# school_shield.net
KiCad netlist of a schematic drawn in EAGLE
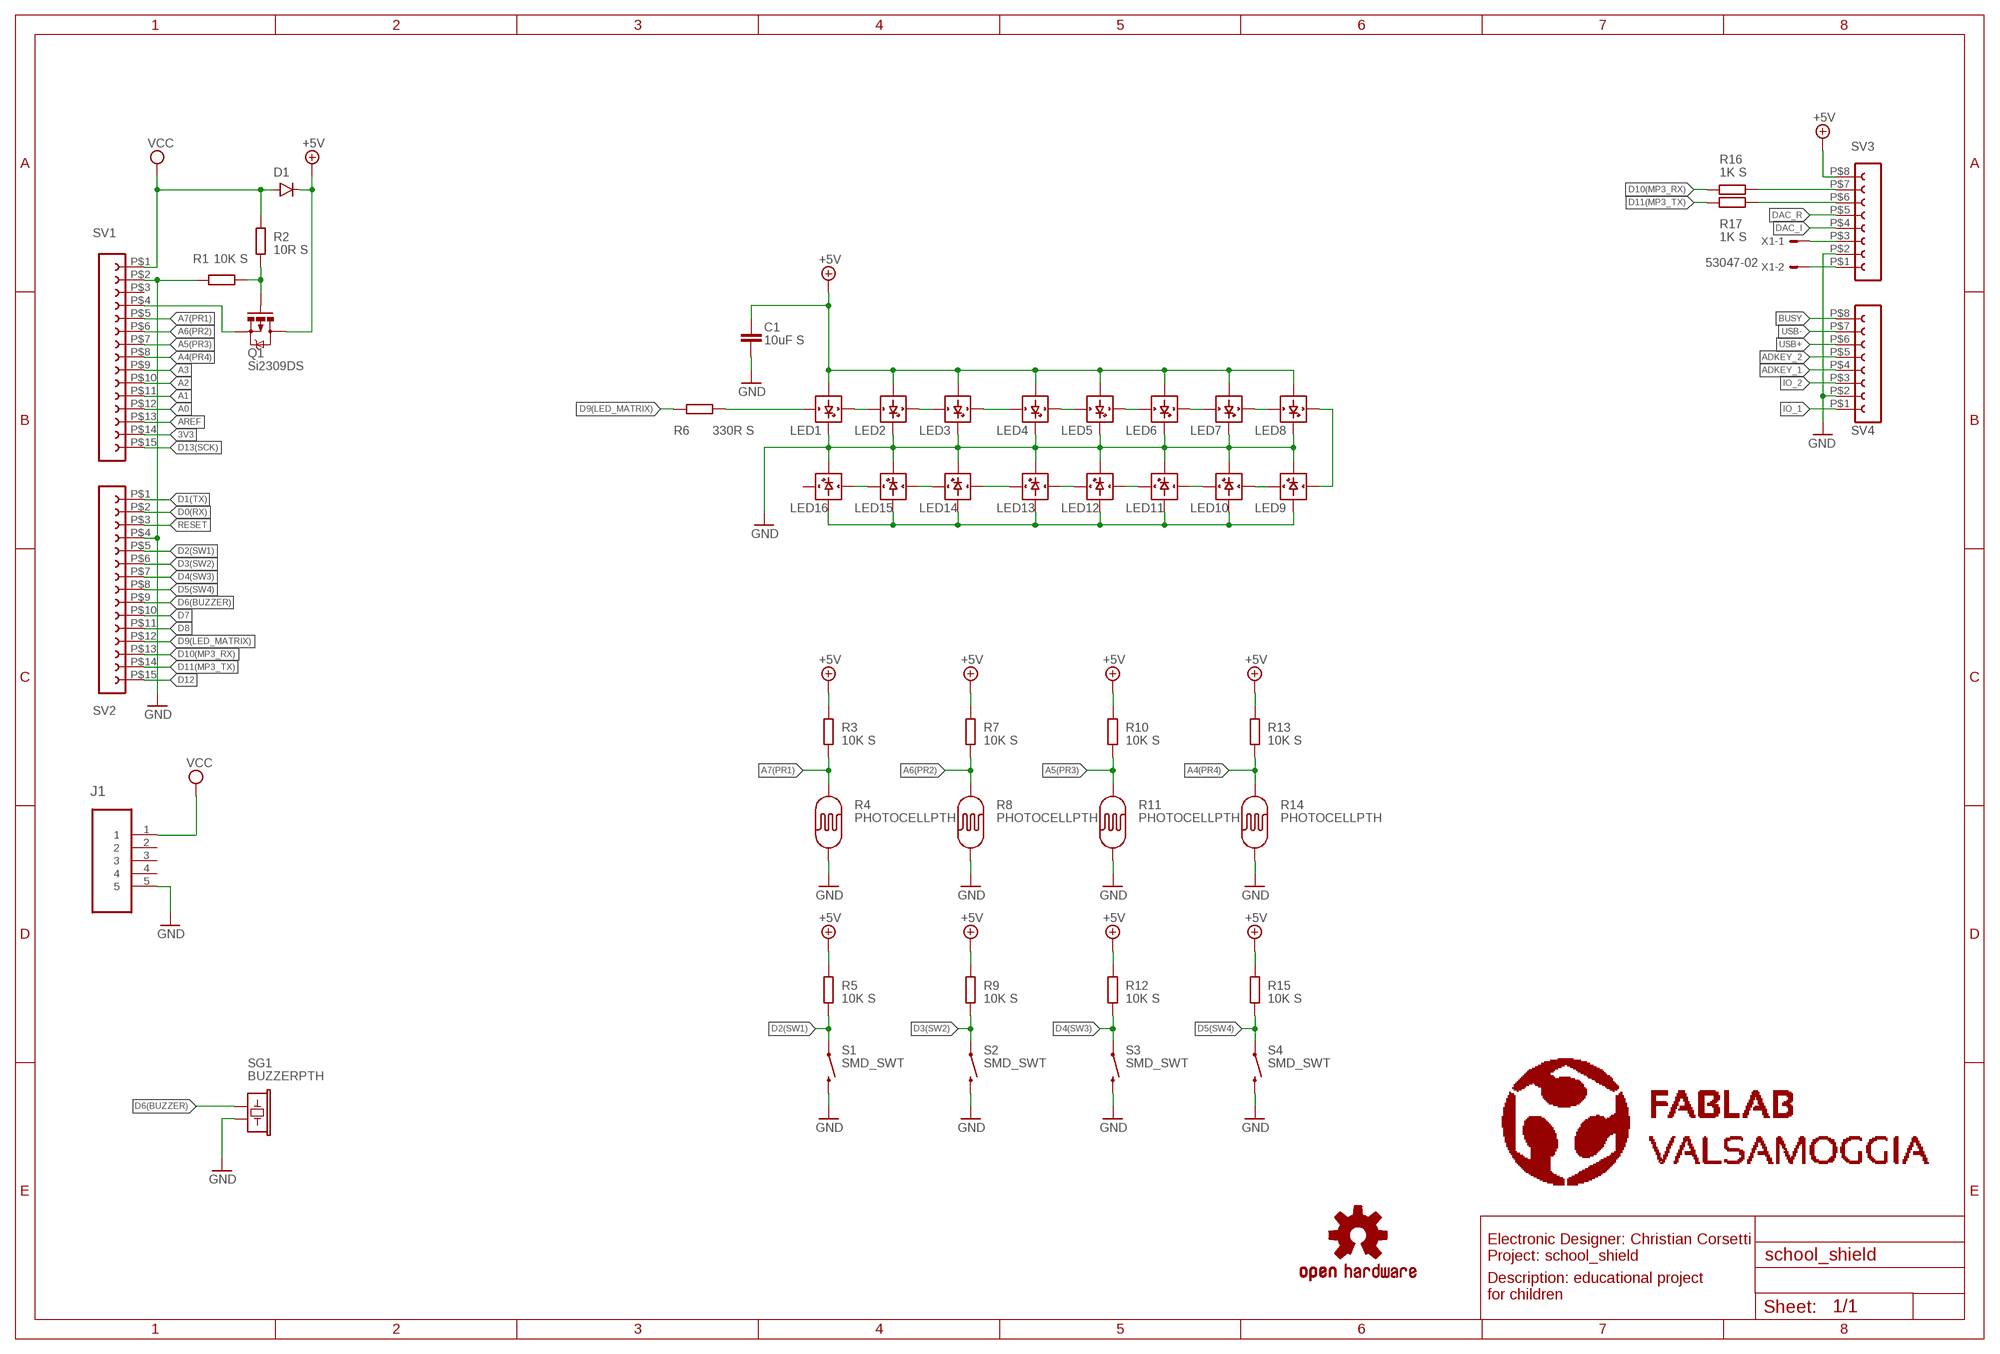
[diagram p0: schematic, sheet 1]

(export (version "E")
  (design (tool "Eeschema 10.0.6"))
  (components
    (comp (ref "C1")
      (value "10uF S")
      (footprint "eagle-import:C0805")
      (libsource (lib "eagle-import") (part "C-EUC0805"))
    )
    (comp (ref "D1")
      (value "DIODESMA")
      (footprint "eagle-import:SMA-DIODE")
      (libsource (lib "eagle-import") (part "DIODESMA"))
    )
    (comp (ref "J1")
      (value "47346-0001")
      (footprint "eagle-import:MOLEX_47346-0001")
      (fields (field (name "SPICEPREFIX") "X"))
      (libsource (lib "eagle-import") (part "47346-0001"))
    )
    (comp (ref "LED1")
      (value "WS2812B_ALT")
      (footprint "eagle-import:WS2812B")
      (libsource (lib "eagle-import") (part "WS2812B_ALT"))
    )
    (comp (ref "LED2")
      (value "WS2812B_ALT")
      (footprint "eagle-import:WS2812B")
      (libsource (lib "eagle-import") (part "WS2812B_ALT"))
    )
    (comp (ref "LED3")
      (value "WS2812B_ALT")
      (footprint "eagle-import:WS2812B")
      (libsource (lib "eagle-import") (part "WS2812B_ALT"))
    )
    (comp (ref "LED4")
      (value "WS2812B_ALT")
      (footprint "eagle-import:WS2812B")
      (libsource (lib "eagle-import") (part "WS2812B_ALT"))
    )
    (comp (ref "LED5")
      (value "WS2812B_ALT")
      (footprint "eagle-import:WS2812B")
      (libsource (lib "eagle-import") (part "WS2812B_ALT"))
    )
    (comp (ref "LED6")
      (value "WS2812B_ALT")
      (footprint "eagle-import:WS2812B")
      (libsource (lib "eagle-import") (part "WS2812B_ALT"))
    )
    (comp (ref "LED7")
      (value "WS2812B_ALT")
      (footprint "eagle-import:WS2812B")
      (libsource (lib "eagle-import") (part "WS2812B_ALT"))
    )
    (comp (ref "LED8")
      (value "WS2812B_ALT")
      (footprint "eagle-import:WS2812B")
      (libsource (lib "eagle-import") (part "WS2812B_ALT"))
    )
    (comp (ref "LED9")
      (value "WS2812B_ALT")
      (footprint "eagle-import:WS2812B")
      (libsource (lib "eagle-import") (part "WS2812B_ALT"))
    )
    (comp (ref "LED10")
      (value "WS2812B_ALT")
      (footprint "eagle-import:WS2812B")
      (libsource (lib "eagle-import") (part "WS2812B_ALT"))
    )
    (comp (ref "LED11")
      (value "WS2812B_ALT")
      (footprint "eagle-import:WS2812B")
      (libsource (lib "eagle-import") (part "WS2812B_ALT"))
    )
    (comp (ref "LED12")
      (value "WS2812B_ALT")
      (footprint "eagle-import:WS2812B")
      (libsource (lib "eagle-import") (part "WS2812B_ALT"))
    )
    (comp (ref "LED13")
      (value "WS2812B_ALT")
      (footprint "eagle-import:WS2812B")
      (libsource (lib "eagle-import") (part "WS2812B_ALT"))
    )
    (comp (ref "LED14")
      (value "WS2812B_ALT")
      (footprint "eagle-import:WS2812B")
      (libsource (lib "eagle-import") (part "WS2812B_ALT"))
    )
    (comp (ref "LED15")
      (value "WS2812B_ALT")
      (footprint "eagle-import:WS2812B")
      (libsource (lib "eagle-import") (part "WS2812B_ALT"))
    )
    (comp (ref "LED16")
      (value "WS2812B_ALT")
      (footprint "eagle-import:WS2812B")
      (libsource (lib "eagle-import") (part "WS2812B_ALT"))
    )
    (comp (ref "LOGO1")
      (value "OSHW-LOGOMINI")
      (footprint "eagle-import:OSHW-LOGO-MINI")
      (libsource (lib "eagle-import") (part "OSHW-LOGOMINI"))
    )
    (comp (ref "Q1")
      (value "Si2309DS")
      (footprint "eagle-import:SOT23-3")
      (libsource (lib "eagle-import") (part "MOSFET-PCHANNELSMD"))
    )
    (comp (ref "R1")
      (value "10K S")
      (footprint "eagle-import:R0805")
      (libsource (lib "eagle-import") (part "R-EU_R0805"))
    )
    (comp (ref "R2")
      (value "10R S")
      (footprint "eagle-import:R0805")
      (libsource (lib "eagle-import") (part "R-EU_R0805"))
    )
    (comp (ref "R3")
      (value "10K S")
      (footprint "eagle-import:R0805")
      (libsource (lib "eagle-import") (part "R-EU_R0805"))
    )
    (comp (ref "R4")
      (value "PHOTOCELLPTH")
      (footprint "eagle-import:PHOTOCELL")
      (libsource (lib "eagle-import") (part "PHOTOCELLPTH"))
    )
    (comp (ref "R5")
      (value "10K S")
      (footprint "eagle-import:R0805")
      (libsource (lib "eagle-import") (part "R-EU_R0805"))
    )
    (comp (ref "R6")
      (value "330R S")
      (footprint "eagle-import:R0805")
      (libsource (lib "eagle-import") (part "R-EU_R0805"))
    )
    (comp (ref "R7")
      (value "10K S")
      (footprint "eagle-import:R0805")
      (libsource (lib "eagle-import") (part "R-EU_R0805"))
    )
    (comp (ref "R8")
      (value "PHOTOCELLPTH")
      (footprint "eagle-import:PHOTOCELL")
      (libsource (lib "eagle-import") (part "PHOTOCELLPTH"))
    )
    (comp (ref "R9")
      (value "10K S")
      (footprint "eagle-import:R0805")
      (libsource (lib "eagle-import") (part "R-EU_R0805"))
    )
    (comp (ref "R10")
      (value "10K S")
      (footprint "eagle-import:R0805")
      (libsource (lib "eagle-import") (part "R-EU_R0805"))
    )
    (comp (ref "R11")
      (value "PHOTOCELLPTH")
      (footprint "eagle-import:PHOTOCELL")
      (libsource (lib "eagle-import") (part "PHOTOCELLPTH"))
    )
    (comp (ref "R12")
      (value "10K S")
      (footprint "eagle-import:R0805")
      (libsource (lib "eagle-import") (part "R-EU_R0805"))
    )
    (comp (ref "R13")
      (value "10K S")
      (footprint "eagle-import:R0805")
      (libsource (lib "eagle-import") (part "R-EU_R0805"))
    )
    (comp (ref "R14")
      (value "PHOTOCELLPTH")
      (footprint "eagle-import:PHOTOCELL")
      (libsource (lib "eagle-import") (part "PHOTOCELLPTH"))
    )
    (comp (ref "R15")
      (value "10K S")
      (footprint "eagle-import:R0805")
      (libsource (lib "eagle-import") (part "R-EU_R0805"))
    )
    (comp (ref "R16")
      (value "1K S")
      (footprint "eagle-import:R0805")
      (libsource (lib "eagle-import") (part "R-EU_R0805"))
    )
    (comp (ref "R17")
      (value "1K S")
      (footprint "eagle-import:R0805")
      (libsource (lib "eagle-import") (part "R-EU_R0805"))
    )
    (comp (ref "S1")
      (value "SMD_SWT")
      (footprint "eagle-import:TACTILE_SWITCH_TALL")
      (libsource (lib "eagle-import") (part "SWITCH-MOMENTARY-2SMD-4"))
    )
    (comp (ref "S2")
      (value "SMD_SWT")
      (footprint "eagle-import:TACTILE_SWITCH_TALL")
      (libsource (lib "eagle-import") (part "SWITCH-MOMENTARY-2SMD-4"))
    )
    (comp (ref "S3")
      (value "SMD_SWT")
      (footprint "eagle-import:TACTILE_SWITCH_TALL")
      (libsource (lib "eagle-import") (part "SWITCH-MOMENTARY-2SMD-4"))
    )
    (comp (ref "S4")
      (value "SMD_SWT")
      (footprint "eagle-import:TACTILE_SWITCH_TALL")
      (libsource (lib "eagle-import") (part "SWITCH-MOMENTARY-2SMD-4"))
    )
    (comp (ref "SG1")
      (value "BUZZERPTH")
      (footprint "eagle-import:BUZZER-12MM")
      (libsource (lib "eagle-import") (part "BUZZERPTH"))
    )
    (comp (ref "SV1")
      (value "FE15-1SMD")
      (footprint "eagle-import:FE15_SMD")
      (libsource (lib "eagle-import") (part "FE15-1SMD"))
    )
    (comp (ref "SV2")
      (value "FE15-1SMD")
      (footprint "eagle-import:FE15_SMD")
      (libsource (lib "eagle-import") (part "FE15-1SMD"))
    )
    (comp (ref "SV3")
      (value "FE08-1SMD")
      (footprint "eagle-import:FE08_SMD")
      (libsource (lib "eagle-import") (part "FE08-1SMD"))
    )
    (comp (ref "SV4")
      (value "FE08-1SMD")
      (footprint "eagle-import:FE08_SMD")
      (libsource (lib "eagle-import") (part "FE08-1SMD"))
    )
    (comp (ref "U$1")
      (value "FABLAB")
      (footprint "eagle-import:FABLAB")
      (libsource (lib "eagle-import") (part "FABLAB"))
    )
    (comp (ref "X1")
      (value "53047-02")
      (footprint "eagle-import:53047-02")
      (libsource (lib "eagle-import") (part "53?-02047"))
    )
  )
  (nets
    (net (code "1") (name "+5V") (class "Default")
      (node (ref "C1") (pin "2") (pinfunction "2_2") (pintype "passive"))
      (node (ref "D1") (pin "C") (pinfunction "C_C") (pintype "passive"))
      (node (ref "LED1") (pin "1-VDD") (pinfunction "VDD_1-VDD") (pintype "bidirectional"))
      (node (ref "LED2") (pin "1-VDD") (pinfunction "VDD_1-VDD") (pintype "bidirectional"))
      (node (ref "LED3") (pin "1-VDD") (pinfunction "VDD_1-VDD") (pintype "bidirectional"))
      (node (ref "LED4") (pin "1-VDD") (pinfunction "VDD_1-VDD") (pintype "bidirectional"))
      (node (ref "LED5") (pin "1-VDD") (pinfunction "VDD_1-VDD") (pintype "bidirectional"))
      (node (ref "LED6") (pin "1-VDD") (pinfunction "VDD_1-VDD") (pintype "bidirectional"))
      (node (ref "LED7") (pin "1-VDD") (pinfunction "VDD_1-VDD") (pintype "bidirectional"))
      (node (ref "LED8") (pin "1-VDD") (pinfunction "VDD_1-VDD") (pintype "bidirectional"))
      (node (ref "Q1") (pin "3") (pinfunction "D_3") (pintype "passive"))
      (node (ref "R10") (pin "2") (pinfunction "2_2") (pintype "passive"))
      (node (ref "R12") (pin "2") (pinfunction "2_2") (pintype "passive"))
      (node (ref "R13") (pin "2") (pinfunction "2_2") (pintype "passive"))
      (node (ref "R15") (pin "2") (pinfunction "2_2") (pintype "passive"))
      (node (ref "R3") (pin "2") (pinfunction "2_2") (pintype "passive"))
      (node (ref "R5") (pin "2") (pinfunction "2_2") (pintype "passive"))
      (node (ref "R7") (pin "2") (pinfunction "2_2") (pintype "passive"))
      (node (ref "R9") (pin "2") (pinfunction "2_2") (pintype "passive"))
      (node (ref "SV3") (pin "P$8") (pinfunction "8_P$8") (pintype "passive"))
    )
    (net (code "2") (name "3V3") (class "Default")
      (node (ref "SV1") (pin "P$14") (pinfunction "14_P$14") (pintype "passive"))
    )
    (net (code "3") (name "A0") (class "Default")
      (node (ref "SV1") (pin "P$12") (pinfunction "12_P$12") (pintype "passive"))
    )
    (net (code "4") (name "A1") (class "Default")
      (node (ref "SV1") (pin "P$11") (pinfunction "11_P$11") (pintype "passive"))
    )
    (net (code "5") (name "A2") (class "Default")
      (node (ref "SV1") (pin "P$10") (pinfunction "10_P$10") (pintype "passive"))
    )
    (net (code "6") (name "A3") (class "Default")
      (node (ref "SV1") (pin "P$9") (pinfunction "9_P$9") (pintype "passive"))
    )
    (net (code "7") (name "A4(PR4)") (class "Default")
      (node (ref "R13") (pin "1") (pinfunction "1_1") (pintype "passive"))
      (node (ref "R14") (pin "2") (pinfunction "P$2_2") (pintype "bidirectional"))
      (node (ref "SV1") (pin "P$8") (pinfunction "8_P$8") (pintype "passive"))
    )
    (net (code "8") (name "A5(PR3)") (class "Default")
      (node (ref "R10") (pin "1") (pinfunction "1_1") (pintype "passive"))
      (node (ref "R11") (pin "2") (pinfunction "P$2_2") (pintype "bidirectional"))
      (node (ref "SV1") (pin "P$7") (pinfunction "7_P$7") (pintype "passive"))
    )
    (net (code "9") (name "A6(PR2)") (class "Default")
      (node (ref "R7") (pin "1") (pinfunction "1_1") (pintype "passive"))
      (node (ref "R8") (pin "2") (pinfunction "P$2_2") (pintype "bidirectional"))
      (node (ref "SV1") (pin "P$6") (pinfunction "6_P$6") (pintype "passive"))
    )
    (net (code "10") (name "A7(PR1)") (class "Default")
      (node (ref "R3") (pin "1") (pinfunction "1_1") (pintype "passive"))
      (node (ref "R4") (pin "2") (pinfunction "P$2_2") (pintype "bidirectional"))
      (node (ref "SV1") (pin "P$5") (pinfunction "5_P$5") (pintype "passive"))
    )
    (net (code "11") (name "ADKEY_1") (class "Default")
      (node (ref "SV4") (pin "P$4") (pinfunction "4_P$4") (pintype "passive"))
    )
    (net (code "12") (name "ADKEY_2") (class "Default")
      (node (ref "SV4") (pin "P$5") (pinfunction "5_P$5") (pintype "passive"))
    )
    (net (code "13") (name "AREF") (class "Default")
      (node (ref "SV1") (pin "P$13") (pinfunction "13_P$13") (pintype "passive"))
    )
    (net (code "14") (name "BUSY") (class "Default")
      (node (ref "SV4") (pin "P$8") (pinfunction "8_P$8") (pintype "passive"))
    )
    (net (code "15") (name "D0(RX)") (class "Default")
      (node (ref "SV2") (pin "P$2") (pinfunction "2_P$2") (pintype "passive"))
    )
    (net (code "16") (name "D1(TX)") (class "Default")
      (node (ref "SV2") (pin "P$1") (pinfunction "1_P$1") (pintype "passive"))
    )
    (net (code "17") (name "D2(SW1)") (class "Default")
      (node (ref "R5") (pin "1") (pinfunction "1_1") (pintype "passive"))
      (node (ref "S1") (pin "A2") (pinfunction "1_A2") (pintype "passive"))
      (node (ref "SV2") (pin "P$5") (pinfunction "5_P$5") (pintype "passive"))
    )
    (net (code "18") (name "D3(SW2)") (class "Default")
      (node (ref "R9") (pin "1") (pinfunction "1_1") (pintype "passive"))
      (node (ref "S2") (pin "A2") (pinfunction "1_A2") (pintype "passive"))
      (node (ref "SV2") (pin "P$6") (pinfunction "6_P$6") (pintype "passive"))
    )
    (net (code "19") (name "D4(SW3)") (class "Default")
      (node (ref "R12") (pin "1") (pinfunction "1_1") (pintype "passive"))
      (node (ref "S3") (pin "A2") (pinfunction "1_A2") (pintype "passive"))
      (node (ref "SV2") (pin "P$7") (pinfunction "7_P$7") (pintype "passive"))
    )
    (net (code "20") (name "D5(SW4)") (class "Default")
      (node (ref "R15") (pin "1") (pinfunction "1_1") (pintype "passive"))
      (node (ref "S4") (pin "A2") (pinfunction "1_A2") (pintype "passive"))
      (node (ref "SV2") (pin "P$8") (pinfunction "8_P$8") (pintype "passive"))
    )
    (net (code "21") (name "D6(BUZZER)") (class "Default")
      (node (ref "SG1") (pin "+") (pinfunction "1_+") (pintype "passive"))
      (node (ref "SV2") (pin "P$9") (pinfunction "9_P$9") (pintype "passive"))
    )
    (net (code "22") (name "D7") (class "Default")
      (node (ref "SV2") (pin "P$10") (pinfunction "10_P$10") (pintype "passive"))
    )
    (net (code "23") (name "D8") (class "Default")
      (node (ref "SV2") (pin "P$11") (pinfunction "11_P$11") (pintype "passive"))
    )
    (net (code "24") (name "D9(LED_MATRIX)") (class "Default")
      (node (ref "R6") (pin "2") (pinfunction "2_2") (pintype "passive"))
      (node (ref "SV2") (pin "P$12") (pinfunction "12_P$12") (pintype "passive"))
    )
    (net (code "25") (name "D10(MP3_RX)") (class "Default")
      (node (ref "R16") (pin "2") (pinfunction "2_2") (pintype "passive"))
      (node (ref "SV2") (pin "P$13") (pinfunction "13_P$13") (pintype "passive"))
    )
    (net (code "26") (name "D11(MP3_TX)") (class "Default")
      (node (ref "R17") (pin "2") (pinfunction "2_2") (pintype "passive"))
      (node (ref "SV2") (pin "P$14") (pinfunction "14_P$14") (pintype "passive"))
    )
    (net (code "27") (name "D12") (class "Default")
      (node (ref "SV2") (pin "P$15") (pinfunction "15_P$15") (pintype "passive"))
    )
    (net (code "28") (name "D13(SCK)") (class "Default")
      (node (ref "SV1") (pin "P$15") (pinfunction "15_P$15") (pintype "passive"))
    )
    (net (code "29") (name "DAC_I") (class "Default")
      (node (ref "SV3") (pin "P$4") (pinfunction "4_P$4") (pintype "passive"))
    )
    (net (code "30") (name "DAC_R") (class "Default")
      (node (ref "SV3") (pin "P$5") (pinfunction "5_P$5") (pintype "passive"))
    )
    (net (code "31") (name "GND") (class "Default")
      (node (ref "C1") (pin "1") (pinfunction "1_1") (pintype "passive"))
      (node (ref "J1") (pin "5") (pinfunction "5_5") (pintype "input"))
      (node (ref "LED1") (pin "3-GND") (pinfunction "GND_3-GND") (pintype "bidirectional"))
      (node (ref "LED10") (pin "3-GND") (pinfunction "GND_3-GND") (pintype "bidirectional"))
      (node (ref "LED11") (pin "3-GND") (pinfunction "GND_3-GND") (pintype "bidirectional"))
      (node (ref "LED12") (pin "3-GND") (pinfunction "GND_3-GND") (pintype "bidirectional"))
      (node (ref "LED13") (pin "3-GND") (pinfunction "GND_3-GND") (pintype "bidirectional"))
      (node (ref "LED14") (pin "3-GND") (pinfunction "GND_3-GND") (pintype "bidirectional"))
      (node (ref "LED15") (pin "3-GND") (pinfunction "GND_3-GND") (pintype "bidirectional"))
      (node (ref "LED16") (pin "3-GND") (pinfunction "GND_3-GND") (pintype "bidirectional"))
      (node (ref "LED2") (pin "3-GND") (pinfunction "GND_3-GND") (pintype "bidirectional"))
      (node (ref "LED3") (pin "3-GND") (pinfunction "GND_3-GND") (pintype "bidirectional"))
      (node (ref "LED4") (pin "3-GND") (pinfunction "GND_3-GND") (pintype "bidirectional"))
      (node (ref "LED5") (pin "3-GND") (pinfunction "GND_3-GND") (pintype "bidirectional"))
      (node (ref "LED6") (pin "3-GND") (pinfunction "GND_3-GND") (pintype "bidirectional"))
      (node (ref "LED7") (pin "3-GND") (pinfunction "GND_3-GND") (pintype "bidirectional"))
      (node (ref "LED8") (pin "3-GND") (pinfunction "GND_3-GND") (pintype "bidirectional"))
      (node (ref "LED9") (pin "3-GND") (pinfunction "GND_3-GND") (pintype "bidirectional"))
      (node (ref "R1") (pin "2") (pinfunction "2_2") (pintype "passive"))
      (node (ref "R11") (pin "1") (pinfunction "P$1_1") (pintype "bidirectional"))
      (node (ref "R14") (pin "1") (pinfunction "P$1_1") (pintype "bidirectional"))
      (node (ref "R4") (pin "1") (pinfunction "P$1_1") (pintype "bidirectional"))
      (node (ref "R8") (pin "1") (pinfunction "P$1_1") (pintype "bidirectional"))
      (node (ref "S1") (pin "B2") (pinfunction "2_B2") (pintype "passive"))
      (node (ref "S2") (pin "B2") (pinfunction "2_B2") (pintype "passive"))
      (node (ref "S3") (pin "B2") (pinfunction "2_B2") (pintype "passive"))
      (node (ref "S4") (pin "B2") (pinfunction "2_B2") (pintype "passive"))
      (node (ref "SG1") (pin "-") (pinfunction "2_-") (pintype "passive"))
      (node (ref "SV1") (pin "P$2") (pinfunction "2_P$2") (pintype "passive"))
      (node (ref "SV2") (pin "P$4") (pinfunction "4_P$4") (pintype "passive"))
      (node (ref "SV3") (pin "P$2") (pinfunction "2_P$2") (pintype "passive"))
      (node (ref "SV4") (pin "P$2") (pinfunction "2_P$2") (pintype "passive"))
    )
    (net (code "32") (name "IO_1") (class "Default")
      (node (ref "SV4") (pin "P$1") (pinfunction "1_P$1") (pintype "passive"))
    )
    (net (code "33") (name "IO_2") (class "Default")
      (node (ref "SV4") (pin "P$3") (pinfunction "3_P$3") (pintype "passive"))
    )
    (net (code "34") (name "Net-(LED1-DIN)") (class "Default")
      (node (ref "LED1") (pin "4-DIN") (pinfunction "DIN_4-DIN") (pintype "input"))
      (node (ref "R6") (pin "1") (pinfunction "1_1") (pintype "passive"))
    )
    (net (code "35") (name "Net-(LED1-DOUT)") (class "Default")
      (node (ref "LED1") (pin "2-DOUT") (pinfunction "DOUT_2-DOUT") (pintype "output"))
      (node (ref "LED2") (pin "4-DIN") (pinfunction "DIN_4-DIN") (pintype "input"))
    )
    (net (code "36") (name "Net-(LED2-DOUT)") (class "Default")
      (node (ref "LED2") (pin "2-DOUT") (pinfunction "DOUT_2-DOUT") (pintype "output"))
      (node (ref "LED3") (pin "4-DIN") (pinfunction "DIN_4-DIN") (pintype "input"))
    )
    (net (code "37") (name "Net-(LED3-DOUT)") (class "Default")
      (node (ref "LED3") (pin "2-DOUT") (pinfunction "DOUT_2-DOUT") (pintype "output"))
      (node (ref "LED4") (pin "4-DIN") (pinfunction "DIN_4-DIN") (pintype "input"))
    )
    (net (code "38") (name "Net-(LED4-DOUT)") (class "Default")
      (node (ref "LED4") (pin "2-DOUT") (pinfunction "DOUT_2-DOUT") (pintype "output"))
      (node (ref "LED5") (pin "4-DIN") (pinfunction "DIN_4-DIN") (pintype "input"))
    )
    (net (code "39") (name "Net-(LED5-DOUT)") (class "Default")
      (node (ref "LED5") (pin "2-DOUT") (pinfunction "DOUT_2-DOUT") (pintype "output"))
      (node (ref "LED6") (pin "4-DIN") (pinfunction "DIN_4-DIN") (pintype "input"))
    )
    (net (code "40") (name "Net-(LED6-DOUT)") (class "Default")
      (node (ref "LED6") (pin "2-DOUT") (pinfunction "DOUT_2-DOUT") (pintype "output"))
      (node (ref "LED7") (pin "4-DIN") (pinfunction "DIN_4-DIN") (pintype "input"))
    )
    (net (code "41") (name "Net-(LED7-DOUT)") (class "Default")
      (node (ref "LED7") (pin "2-DOUT") (pinfunction "DOUT_2-DOUT") (pintype "output"))
      (node (ref "LED8") (pin "4-DIN") (pinfunction "DIN_4-DIN") (pintype "input"))
    )
    (net (code "42") (name "Net-(LED8-DOUT)") (class "Default")
      (node (ref "LED8") (pin "2-DOUT") (pinfunction "DOUT_2-DOUT") (pintype "output"))
      (node (ref "LED9") (pin "4-DIN") (pinfunction "DIN_4-DIN") (pintype "input"))
    )
    (net (code "43") (name "Net-(LED10-DIN)") (class "Default")
      (node (ref "LED10") (pin "4-DIN") (pinfunction "DIN_4-DIN") (pintype "input"))
      (node (ref "LED9") (pin "2-DOUT") (pinfunction "DOUT_2-DOUT") (pintype "output"))
    )
    (net (code "44") (name "Net-(LED10-DOUT)") (class "Default")
      (node (ref "LED10") (pin "2-DOUT") (pinfunction "DOUT_2-DOUT") (pintype "output"))
      (node (ref "LED11") (pin "4-DIN") (pinfunction "DIN_4-DIN") (pintype "input"))
    )
    (net (code "45") (name "Net-(LED10-VDD)") (class "Default")
      (node (ref "LED10") (pin "1-VDD") (pinfunction "VDD_1-VDD") (pintype "bidirectional"))
      (node (ref "LED11") (pin "1-VDD") (pinfunction "VDD_1-VDD") (pintype "bidirectional"))
      (node (ref "LED12") (pin "1-VDD") (pinfunction "VDD_1-VDD") (pintype "bidirectional"))
      (node (ref "LED13") (pin "1-VDD") (pinfunction "VDD_1-VDD") (pintype "bidirectional"))
      (node (ref "LED14") (pin "1-VDD") (pinfunction "VDD_1-VDD") (pintype "bidirectional"))
      (node (ref "LED15") (pin "1-VDD") (pinfunction "VDD_1-VDD") (pintype "bidirectional"))
      (node (ref "LED16") (pin "1-VDD") (pinfunction "VDD_1-VDD") (pintype "bidirectional"))
      (node (ref "LED9") (pin "1-VDD") (pinfunction "VDD_1-VDD") (pintype "bidirectional"))
    )
    (net (code "46") (name "Net-(LED11-DOUT)") (class "Default")
      (node (ref "LED11") (pin "2-DOUT") (pinfunction "DOUT_2-DOUT") (pintype "output"))
      (node (ref "LED12") (pin "4-DIN") (pinfunction "DIN_4-DIN") (pintype "input"))
    )
    (net (code "47") (name "Net-(LED12-DOUT)") (class "Default")
      (node (ref "LED12") (pin "2-DOUT") (pinfunction "DOUT_2-DOUT") (pintype "output"))
      (node (ref "LED13") (pin "4-DIN") (pinfunction "DIN_4-DIN") (pintype "input"))
    )
    (net (code "48") (name "Net-(LED13-DOUT)") (class "Default")
      (node (ref "LED13") (pin "2-DOUT") (pinfunction "DOUT_2-DOUT") (pintype "output"))
      (node (ref "LED14") (pin "4-DIN") (pinfunction "DIN_4-DIN") (pintype "input"))
    )
    (net (code "49") (name "Net-(LED14-DOUT)") (class "Default")
      (node (ref "LED14") (pin "2-DOUT") (pinfunction "DOUT_2-DOUT") (pintype "output"))
      (node (ref "LED15") (pin "4-DIN") (pinfunction "DIN_4-DIN") (pintype "input"))
    )
    (net (code "50") (name "Net-(LED15-DOUT)") (class "Default")
      (node (ref "LED15") (pin "2-DOUT") (pinfunction "DOUT_2-DOUT") (pintype "output"))
      (node (ref "LED16") (pin "4-DIN") (pinfunction "DIN_4-DIN") (pintype "input"))
    )
    (net (code "51") (name "Net-(Q1-G)") (class "Default")
      (node (ref "Q1") (pin "1") (pinfunction "G_1") (pintype "passive"))
      (node (ref "R1") (pin "1") (pinfunction "1_1") (pintype "passive"))
      (node (ref "R2") (pin "2") (pinfunction "2_2") (pintype "passive"))
    )
    (net (code "52") (name "Net-(Q1-S)") (class "Default")
      (node (ref "Q1") (pin "2") (pinfunction "S_2") (pintype "passive"))
      (node (ref "SV1") (pin "P$4") (pinfunction "4_P$4") (pintype "passive"))
    )
    (net (code "53") (name "Net-(SV3-1)") (class "Default")
      (node (ref "SV3") (pin "P$1") (pinfunction "1_P$1") (pintype "passive"))
      (node (ref "X1") (pin "2") (pinfunction "S_2") (pintype "passive"))
    )
    (net (code "54") (name "Net-(SV3-3)") (class "Default")
      (node (ref "SV3") (pin "P$3") (pinfunction "3_P$3") (pintype "passive"))
      (node (ref "X1") (pin "1") (pinfunction "S_1") (pintype "passive"))
    )
    (net (code "55") (name "Net-(SV3-6)") (class "Default")
      (node (ref "R17") (pin "1") (pinfunction "1_1") (pintype "passive"))
      (node (ref "SV3") (pin "P$6") (pinfunction "6_P$6") (pintype "passive"))
    )
    (net (code "56") (name "Net-(SV3-7)") (class "Default")
      (node (ref "R16") (pin "1") (pinfunction "1_1") (pintype "passive"))
      (node (ref "SV3") (pin "P$7") (pinfunction "7_P$7") (pintype "passive"))
    )
    (net (code "57") (name "RESET") (class "Default")
      (node (ref "SV2") (pin "P$3") (pinfunction "3_P$3") (pintype "passive"))
    )
    (net (code "58") (name "USB+") (class "Default")
      (node (ref "SV4") (pin "P$6") (pinfunction "6_P$6") (pintype "passive"))
    )
    (net (code "59") (name "USB-") (class "Default")
      (node (ref "SV4") (pin "P$7") (pinfunction "7_P$7") (pintype "passive"))
    )
    (net (code "60") (name "VCC") (class "Default")
      (node (ref "D1") (pin "A") (pinfunction "A_A") (pintype "passive"))
      (node (ref "J1") (pin "1") (pinfunction "1_1") (pintype "input"))
      (node (ref "R2") (pin "1") (pinfunction "1_1") (pintype "passive"))
      (node (ref "SV1") (pin "P$1") (pinfunction "1_P$1") (pintype "passive"))
    )
    (net (code "61") (name "unconnected-(J1-Pad2)") (class "Default")
      (node (ref "J1") (pin "2") (pinfunction "2_2") (pintype "input"))
    )
    (net (code "62") (name "unconnected-(J1-Pad3)") (class "Default")
      (node (ref "J1") (pin "3") (pinfunction "3_3") (pintype "input"))
    )
    (net (code "63") (name "unconnected-(J1-Pad4)") (class "Default")
      (node (ref "J1") (pin "4") (pinfunction "4_4") (pintype "input"))
    )
    (net (code "64") (name "unconnected-(LED16-DOUT-Pad2-DOUT)") (class "Default")
      (node (ref "LED16") (pin "2-DOUT") (pinfunction "DOUT_2-DOUT") (pintype "output"))
    )
    (net (code "65") (name "unconnected-(SV1-3-PadP$3)") (class "Default")
      (node (ref "SV1") (pin "P$3") (pinfunction "3_P$3") (pintype "passive"))
    )
  )
)
